# micro-stepper-driver-v1.net
KiCad netlist of a schematic drawn in EAGLE
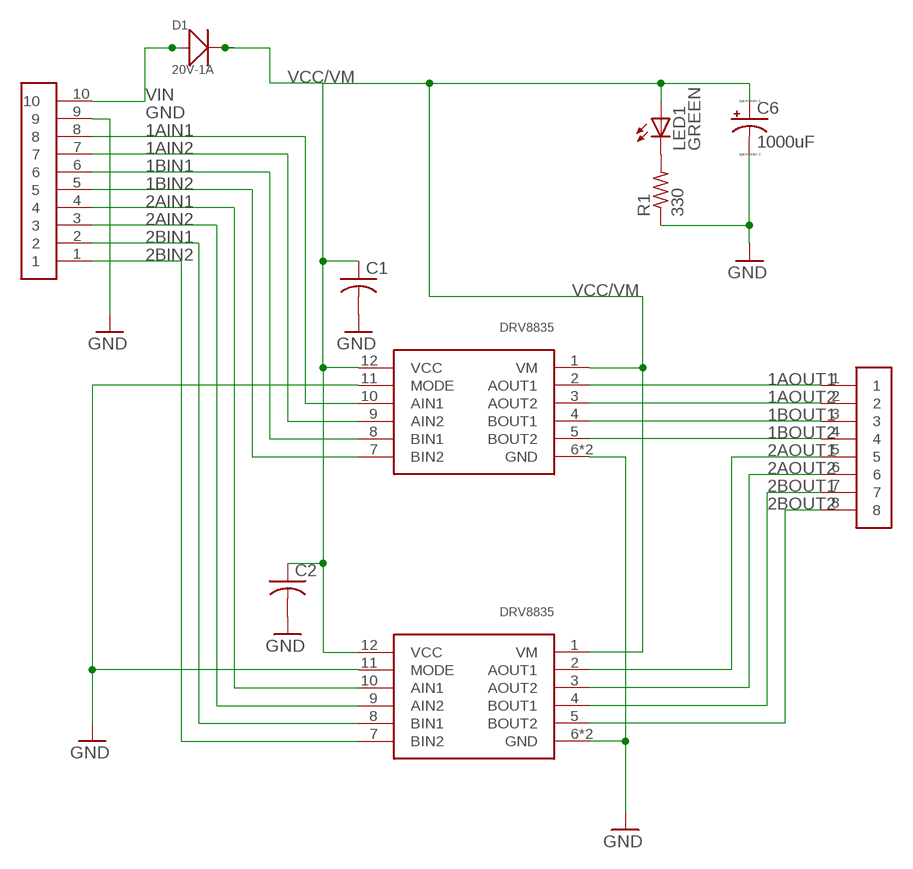
[diagram p0: schematic, sheet 1]

(export (version "E")
  (design (tool "Eeschema 10.0.6"))
  (components
    (comp (ref "C1")
      (value "C-USC0402K")
      (footprint "eagle-import:C0402K")
      (libsource (lib "eagle-import") (part "C-USC0402K"))
    )
    (comp (ref "C2")
      (value "C-USC0402K")
      (footprint "eagle-import:C0402K")
      (libsource (lib "eagle-import") (part "C-USC0402K"))
    )
    (comp (ref "C6")
      (value "1000uF")
      (footprint "eagle-import:153CLV-0810")
      (libsource (lib "eagle-import") (part "CPOL-US153CLV-0810"))
    )
    (comp (ref "D1")
      (value "20V-1A")
      (footprint "eagle-import:SOD-123")
      (fields (field (name "MPN") "B5819W"))
      (libsource (lib "eagle-import") (part "SMD-DIODE-SCHOTTKY-20V-1A(SOD-123)"))
    )
    (comp (ref "LED1")
      (value "GREEN")
      (footprint "eagle-import:SML0603")
      (libsource (lib "eagle-import") (part "LEDSML0603"))
    )
    (comp (ref "R1")
      (value "330")
      (footprint "eagle-import:R0402")
      (libsource (lib "eagle-import") (part "R-US_R0402"))
    )
    (comp (ref "U$1")
      (value "DRV8835")
      (footprint "eagle-import:DRV8835")
      (libsource (lib "eagle-import") (part "DRV8835"))
    )
    (comp (ref "U$2")
      (value "EDGE_MOUNT_HEADER_X10")
      (footprint "eagle-import:EDGE_MOUNT_HEAD_X10")
      (libsource (lib "eagle-import") (part "EDGE_MOUNT_HEADER_X10"))
    )
    (comp (ref "U$3")
      (value "EDGE_MOUNT_HEAD_X8")
      (footprint "eagle-import:EDGE_MOUNT_HEAD_X8")
      (libsource (lib "eagle-import") (part "EDGE_MOUNT_HEAD_X8"))
    )
    (comp (ref "U$4")
      (value "DRV8835")
      (footprint "eagle-import:DRV8835")
      (libsource (lib "eagle-import") (part "DRV8835"))
    )
  )
  (nets
    (net (code "1") (name "/1AIN1") (class "Default")
      (node (ref "U$2") (pin "8") (pinfunction "8_8") (pintype "bidirectional"))
      (node (ref "U$4") (pin "10") (pinfunction "AIN1_10") (pintype "bidirectional"))
    )
    (net (code "2") (name "/1AIN2") (class "Default")
      (node (ref "U$2") (pin "7") (pinfunction "7_7") (pintype "bidirectional"))
      (node (ref "U$4") (pin "9") (pinfunction "AIN2_9") (pintype "bidirectional"))
    )
    (net (code "3") (name "/1AOUT1") (class "Default")
      (node (ref "U$3") (pin "1") (pinfunction "1_1") (pintype "bidirectional"))
      (node (ref "U$4") (pin "2") (pinfunction "AOUT1_2") (pintype "bidirectional"))
    )
    (net (code "4") (name "/1AOUT2") (class "Default")
      (node (ref "U$3") (pin "2") (pinfunction "2_2") (pintype "bidirectional"))
      (node (ref "U$4") (pin "3") (pinfunction "AOUT2_3") (pintype "bidirectional"))
    )
    (net (code "5") (name "/1BIN1") (class "Default")
      (node (ref "U$2") (pin "6") (pinfunction "6_6") (pintype "bidirectional"))
      (node (ref "U$4") (pin "8") (pinfunction "BIN1_8") (pintype "bidirectional"))
    )
    (net (code "6") (name "/1BIN2") (class "Default")
      (node (ref "U$2") (pin "5") (pinfunction "5_5") (pintype "bidirectional"))
      (node (ref "U$4") (pin "7") (pinfunction "BIN2_7") (pintype "bidirectional"))
    )
    (net (code "7") (name "/1BOUT1") (class "Default")
      (node (ref "U$3") (pin "3") (pinfunction "3_3") (pintype "bidirectional"))
      (node (ref "U$4") (pin "4") (pinfunction "BOUT1_4") (pintype "bidirectional"))
    )
    (net (code "8") (name "/1BOUT2") (class "Default")
      (node (ref "U$3") (pin "4") (pinfunction "4_4") (pintype "bidirectional"))
      (node (ref "U$4") (pin "5") (pinfunction "BOUT2_5") (pintype "bidirectional"))
    )
    (net (code "9") (name "/2AIN1") (class "Default")
      (node (ref "U$1") (pin "10") (pinfunction "AIN1_10") (pintype "bidirectional"))
      (node (ref "U$2") (pin "4") (pinfunction "4_4") (pintype "bidirectional"))
    )
    (net (code "10") (name "/2AIN2") (class "Default")
      (node (ref "U$1") (pin "9") (pinfunction "AIN2_9") (pintype "bidirectional"))
      (node (ref "U$2") (pin "3") (pinfunction "3_3") (pintype "bidirectional"))
    )
    (net (code "11") (name "/2AOUT1") (class "Default")
      (node (ref "U$1") (pin "2") (pinfunction "AOUT1_2") (pintype "bidirectional"))
      (node (ref "U$3") (pin "5") (pinfunction "5_5") (pintype "bidirectional"))
    )
    (net (code "12") (name "/2AOUT2") (class "Default")
      (node (ref "U$1") (pin "3") (pinfunction "AOUT2_3") (pintype "bidirectional"))
      (node (ref "U$3") (pin "6") (pinfunction "6_6") (pintype "bidirectional"))
    )
    (net (code "13") (name "/2BIN1") (class "Default")
      (node (ref "U$1") (pin "8") (pinfunction "BIN1_8") (pintype "bidirectional"))
      (node (ref "U$2") (pin "2") (pinfunction "2_2") (pintype "bidirectional"))
    )
    (net (code "14") (name "/2BIN2") (class "Default")
      (node (ref "U$1") (pin "7") (pinfunction "BIN2_7") (pintype "bidirectional"))
      (node (ref "U$2") (pin "1") (pinfunction "1_1") (pintype "bidirectional"))
    )
    (net (code "15") (name "/2BOUT1") (class "Default")
      (node (ref "U$1") (pin "4") (pinfunction "BOUT1_4") (pintype "bidirectional"))
      (node (ref "U$3") (pin "7") (pinfunction "7_7") (pintype "bidirectional"))
    )
    (net (code "16") (name "/2BOUT2") (class "Default")
      (node (ref "U$1") (pin "5") (pinfunction "BOUT2_5") (pintype "bidirectional"))
      (node (ref "U$3") (pin "8") (pinfunction "8_8") (pintype "bidirectional"))
    )
    (net (code "17") (name "/VCC{slash}VM") (class "Default")
      (node (ref "C1") (pin "1") (pinfunction "1_1") (pintype "passive"))
      (node (ref "C2") (pin "1") (pinfunction "1_1") (pintype "passive"))
      (node (ref "C6") (pin "+") (pinfunction "+_+") (pintype "passive"))
      (node (ref "D1") (pin "-") (pinfunction "-_-") (pintype "passive"))
      (node (ref "LED1") (pin "A") (pinfunction "A_A") (pintype "passive"))
      (node (ref "U$1") (pin "1") (pinfunction "VM_1") (pintype "bidirectional"))
      (node (ref "U$1") (pin "12") (pinfunction "VCC_12") (pintype "bidirectional"))
      (node (ref "U$4") (pin "1") (pinfunction "VM_1") (pintype "bidirectional"))
      (node (ref "U$4") (pin "12") (pinfunction "VCC_12") (pintype "bidirectional"))
    )
    (net (code "18") (name "/VIN") (class "Default")
      (node (ref "D1") (pin "+") (pinfunction "+_+") (pintype "passive"))
      (node (ref "U$2") (pin "10") (pinfunction "10_10") (pintype "bidirectional"))
    )
    (net (code "19") (name "GND") (class "Default")
      (node (ref "C1") (pin "2") (pinfunction "2_2") (pintype "passive"))
      (node (ref "C2") (pin "2") (pinfunction "2_2") (pintype "passive"))
      (node (ref "C6") (pin "-") (pinfunction "-_-") (pintype "passive"))
      (node (ref "R1") (pin "1") (pinfunction "1_1") (pintype "passive"))
      (node (ref "U$1") (pin "11") (pinfunction "MODE_11") (pintype "bidirectional"))
      (node (ref "U$1") (pin "6") (pinfunction "GND_6") (pintype "bidirectional"))
      (node (ref "U$1") (pin "PAD") (pinfunction "GND_PAD") (pintype "bidirectional"))
      (node (ref "U$2") (pin "9") (pinfunction "9_9") (pintype "bidirectional"))
      (node (ref "U$4") (pin "11") (pinfunction "MODE_11") (pintype "bidirectional"))
      (node (ref "U$4") (pin "6") (pinfunction "GND_6") (pintype "bidirectional"))
      (node (ref "U$4") (pin "PAD") (pinfunction "GND_PAD") (pintype "bidirectional"))
    )
    (net (code "20") (name "Net-(LED1-PadC)") (class "Default")
      (node (ref "LED1") (pin "C") (pinfunction "C_C") (pintype "passive"))
      (node (ref "R1") (pin "2") (pinfunction "2_2") (pintype "passive"))
    )
  )
)
